# Avalon_PDU.net
KiCad netlist of a schematic drawn in Altium Designer
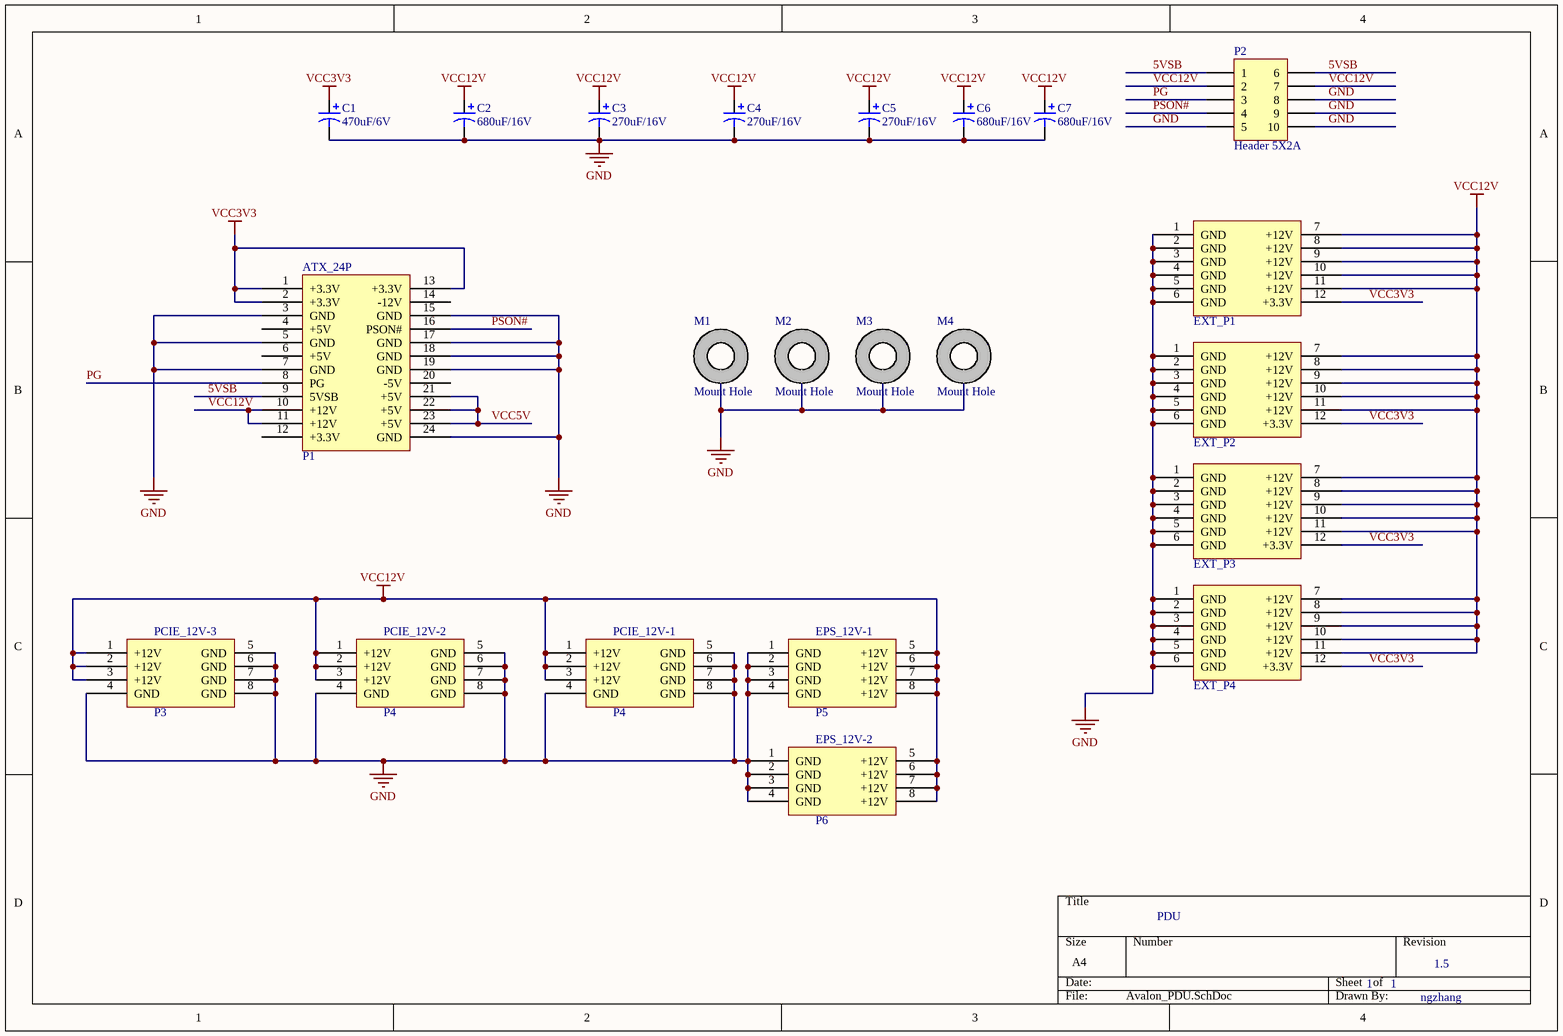
[diagram p0: Avalon_PDU.SchDoc]

(export (version "E")
  (design (tool "Eeschema 10.0.6"))
  (components
    (comp (ref "ATX_24P")
      (value "P1")
      (footprint "ATX_24P")
      (libsource (lib "power_adapter") (part "ATX_24P"))
    )
    (comp (ref "C1")
      (value "470uF/6V")
      (footprint "CAP8X8")
      (description "Polarized Capacitor (Surface Mount)")
      (fields (field (name "PUBLISHER") "Altium Limited"))
      (libsource (lib "S6_2") (part "Cap Pol3"))
    )
    (comp (ref "C2")
      (value "680uF/16V")
      (footprint "CAP8X8")
      (description "Polarized Capacitor (Surface Mount)")
      (fields (field (name "PUBLISHER") "Altium Limited"))
      (libsource (lib "S6_2") (part "Cap Pol3"))
    )
    (comp (ref "C3")
      (value "270uF/16V")
      (footprint "CAP8X8")
      (description "Polarized Capacitor (Surface Mount)")
      (fields (field (name "PUBLISHER") "Altium Limited"))
      (libsource (lib "S6_2") (part "Cap Pol3"))
    )
    (comp (ref "C4")
      (value "270uF/16V")
      (footprint "CAP8X8")
      (description "Polarized Capacitor (Surface Mount)")
      (fields (field (name "PUBLISHER") "Altium Limited"))
      (libsource (lib "S6_2") (part "Cap Pol3"))
    )
    (comp (ref "C5")
      (value "270uF/16V")
      (footprint "CAP8X8")
      (description "Polarized Capacitor (Surface Mount)")
      (fields (field (name "PUBLISHER") "Altium Limited"))
      (libsource (lib "S6_2") (part "Cap Pol3"))
    )
    (comp (ref "C6")
      (value "680uF/16V")
      (footprint "CAP8X8")
      (description "Polarized Capacitor (Surface Mount)")
      (fields (field (name "PUBLISHER") "Altium Limited"))
      (libsource (lib "S6_2") (part "Cap Pol3"))
    )
    (comp (ref "C7")
      (value "680uF/16V")
      (footprint "CAP8X8")
      (description "Polarized Capacitor (Surface Mount)")
      (fields (field (name "PUBLISHER") "Altium Limited"))
      (libsource (lib "S6_2") (part "Cap Pol3"))
    )
    (comp (ref "EPS_12V-1")
      (value "P5")
      (footprint "EPS_12V")
      (libsource (lib "power_adapter") (part "EPS_12V"))
    )
    (comp (ref "EPS_12V-2")
      (value "P6")
      (footprint "EPS_12V")
      (libsource (lib "power_adapter") (part "EPS_12V"))
    )
    (comp (ref "EXT_P1")
      (value "PWR_12P")
      (footprint "PWR_12PIN")
      (libsource (lib "power_adapter") (part "PWR_12P"))
    )
    (comp (ref "EXT_P2")
      (value "PWR_12P")
      (footprint "PWR_12PIN")
      (libsource (lib "power_adapter") (part "PWR_12P"))
    )
    (comp (ref "EXT_P3")
      (value "PWR_12P")
      (footprint "PWR_12PIN")
      (libsource (lib "power_adapter") (part "PWR_12P"))
    )
    (comp (ref "EXT_P4")
      (value "PWR_12P")
      (footprint "PWR_12PIN")
      (libsource (lib "power_adapter") (part "PWR_12P"))
    )
    (comp (ref "M1") (value "Mount Hole") (footprint "MHOLE2") (libsource (lib "S6_2") (part "M_Hole")))
    (comp (ref "M2") (value "Mount Hole") (footprint "MHOLE2") (libsource (lib "S6_2") (part "M_Hole")))
    (comp (ref "M3") (value "Mount Hole") (footprint "MHOLE2") (libsource (lib "S6_2") (part "M_Hole")))
    (comp (ref "M4") (value "Mount Hole") (footprint "MHOLE2") (libsource (lib "S6_2") (part "M_Hole")))
    (comp (ref "P2")
      (value "Header 5X2A")
      (footprint "PWR_10PIN")
      (description "Header, 5-Pin, Dual row")
      (fields (field (name "PUBLISHER") "Altium Limited"))
      (libsource (lib "Miscellaneous Connectors") (part "Header 5X2A"))
    )
    (comp (ref "PCIE_12V-1")
      (value "P4")
      (footprint "PCIE_12V_V")
      (libsource (lib "power_adapter") (part "PCIE_12V"))
    )
    (comp (ref "PCIE_12V-2")
      (value "P4")
      (footprint "PCIE_12V_V")
      (libsource (lib "power_adapter") (part "PCIE_12V"))
    )
    (comp (ref "PCIE_12V-3")
      (value "P3")
      (footprint "PCIE_12V_V")
      (libsource (lib "power_adapter") (part "PCIE_12V"))
    )
  )
  (nets
    (net (code "1") (name "/5VSB") (class "Default")
      (node (ref "ATX_24P") (pin "9") (pinfunction "5VSB_9") (pintype "passive"))
      (node (ref "P2") (pin "1") (pinfunction "1_1") (pintype "passive"))
      (node (ref "P2") (pin "6") (pinfunction "6_6") (pintype "passive"))
    )
    (net (code "2") (name "/PG") (class "Default")
      (node (ref "ATX_24P") (pin "8") (pinfunction "PG_8") (pintype "passive"))
      (node (ref "P2") (pin "3") (pinfunction "3_3") (pintype "passive"))
    )
    (net (code "3") (name "/PSON#") (class "Default")
      (node (ref "ATX_24P") (pin "16") (pinfunction "PSON#_16") (pintype "passive"))
      (node (ref "P2") (pin "4") (pinfunction "4_4") (pintype "passive"))
    )
    (net (code "4") (name "/VCC5V") (class "Default")
      (node (ref "ATX_24P") (pin "21") (pinfunction "+5V_21") (pintype "passive"))
      (node (ref "ATX_24P") (pin "22") (pinfunction "+5V_22") (pintype "passive"))
      (node (ref "ATX_24P") (pin "23") (pinfunction "+5V_23") (pintype "passive"))
    )
    (net (code "5") (name "GND") (class "Default")
      (node (ref "ATX_24P") (pin "15") (pinfunction "GND_15") (pintype "passive"))
      (node (ref "ATX_24P") (pin "17") (pinfunction "GND_17") (pintype "passive"))
      (node (ref "ATX_24P") (pin "18") (pinfunction "GND_18") (pintype "passive"))
      (node (ref "ATX_24P") (pin "19") (pinfunction "GND_19") (pintype "passive"))
      (node (ref "ATX_24P") (pin "24") (pinfunction "GND_24") (pintype "passive"))
      (node (ref "ATX_24P") (pin "3") (pinfunction "GND_3") (pintype "passive"))
      (node (ref "ATX_24P") (pin "5") (pinfunction "GND_5") (pintype "passive"))
      (node (ref "ATX_24P") (pin "7") (pinfunction "GND_7") (pintype "passive"))
      (node (ref "C1") (pin "2") (pinfunction "2_2") (pintype "passive"))
      (node (ref "C2") (pin "2") (pinfunction "2_2") (pintype "passive"))
      (node (ref "C3") (pin "2") (pinfunction "2_2") (pintype "passive"))
      (node (ref "C4") (pin "2") (pinfunction "2_2") (pintype "passive"))
      (node (ref "C5") (pin "2") (pinfunction "2_2") (pintype "passive"))
      (node (ref "C6") (pin "2") (pinfunction "2_2") (pintype "passive"))
      (node (ref "C7") (pin "2") (pinfunction "2_2") (pintype "passive"))
      (node (ref "EPS_12V-1") (pin "1") (pinfunction "GND_1") (pintype "passive"))
      (node (ref "EPS_12V-1") (pin "2") (pinfunction "GND_2") (pintype "passive"))
      (node (ref "EPS_12V-1") (pin "3") (pinfunction "GND_3") (pintype "passive"))
      (node (ref "EPS_12V-1") (pin "4") (pinfunction "GND_4") (pintype "passive"))
      (node (ref "EPS_12V-2") (pin "1") (pinfunction "GND_1") (pintype "passive"))
      (node (ref "EPS_12V-2") (pin "2") (pinfunction "GND_2") (pintype "passive"))
      (node (ref "EPS_12V-2") (pin "3") (pinfunction "GND_3") (pintype "passive"))
      (node (ref "EPS_12V-2") (pin "4") (pinfunction "GND_4") (pintype "passive"))
      (node (ref "EXT_P1") (pin "1") (pinfunction "GND_1") (pintype "passive"))
      (node (ref "EXT_P1") (pin "2") (pinfunction "GND_2") (pintype "passive"))
      (node (ref "EXT_P1") (pin "3") (pinfunction "GND_3") (pintype "passive"))
      (node (ref "EXT_P1") (pin "4") (pinfunction "GND_4") (pintype "passive"))
      (node (ref "EXT_P1") (pin "5") (pinfunction "GND_5") (pintype "passive"))
      (node (ref "EXT_P1") (pin "6") (pinfunction "GND_6") (pintype "passive"))
      (node (ref "EXT_P2") (pin "1") (pinfunction "GND_1") (pintype "passive"))
      (node (ref "EXT_P2") (pin "2") (pinfunction "GND_2") (pintype "passive"))
      (node (ref "EXT_P2") (pin "3") (pinfunction "GND_3") (pintype "passive"))
      (node (ref "EXT_P2") (pin "4") (pinfunction "GND_4") (pintype "passive"))
      (node (ref "EXT_P2") (pin "5") (pinfunction "GND_5") (pintype "passive"))
      (node (ref "EXT_P2") (pin "6") (pinfunction "GND_6") (pintype "passive"))
      (node (ref "EXT_P3") (pin "1") (pinfunction "GND_1") (pintype "passive"))
      (node (ref "EXT_P3") (pin "2") (pinfunction "GND_2") (pintype "passive"))
      (node (ref "EXT_P3") (pin "3") (pinfunction "GND_3") (pintype "passive"))
      (node (ref "EXT_P3") (pin "4") (pinfunction "GND_4") (pintype "passive"))
      (node (ref "EXT_P3") (pin "5") (pinfunction "GND_5") (pintype "passive"))
      (node (ref "EXT_P3") (pin "6") (pinfunction "GND_6") (pintype "passive"))
      (node (ref "EXT_P4") (pin "1") (pinfunction "GND_1") (pintype "passive"))
      (node (ref "EXT_P4") (pin "2") (pinfunction "GND_2") (pintype "passive"))
      (node (ref "EXT_P4") (pin "3") (pinfunction "GND_3") (pintype "passive"))
      (node (ref "EXT_P4") (pin "4") (pinfunction "GND_4") (pintype "passive"))
      (node (ref "EXT_P4") (pin "5") (pinfunction "GND_5") (pintype "passive"))
      (node (ref "EXT_P4") (pin "6") (pinfunction "GND_6") (pintype "passive"))
      (node (ref "M1") (pin "0") (pinfunction "PIN_0") (pintype "power_in"))
      (node (ref "M2") (pin "0") (pinfunction "PIN_0") (pintype "power_in"))
      (node (ref "M3") (pin "0") (pinfunction "PIN_0") (pintype "power_in"))
      (node (ref "M4") (pin "0") (pinfunction "PIN_0") (pintype "power_in"))
      (node (ref "P2") (pin "10") (pinfunction "10_10") (pintype "passive"))
      (node (ref "P2") (pin "5") (pinfunction "5_5") (pintype "passive"))
      (node (ref "P2") (pin "8") (pinfunction "8_8") (pintype "passive"))
      (node (ref "P2") (pin "9") (pinfunction "9_9") (pintype "passive"))
      (node (ref "PCIE_12V-1") (pin "4") (pinfunction "GND_4") (pintype "passive"))
      (node (ref "PCIE_12V-1") (pin "5") (pinfunction "GND_5") (pintype "passive"))
      (node (ref "PCIE_12V-1") (pin "6") (pinfunction "GND_6") (pintype "passive"))
      (node (ref "PCIE_12V-1") (pin "7") (pinfunction "GND_7") (pintype "passive"))
      (node (ref "PCIE_12V-1") (pin "8") (pinfunction "GND_8") (pintype "passive"))
      (node (ref "PCIE_12V-2") (pin "4") (pinfunction "GND_4") (pintype "passive"))
      (node (ref "PCIE_12V-2") (pin "5") (pinfunction "GND_5") (pintype "passive"))
      (node (ref "PCIE_12V-2") (pin "6") (pinfunction "GND_6") (pintype "passive"))
      (node (ref "PCIE_12V-2") (pin "7") (pinfunction "GND_7") (pintype "passive"))
      (node (ref "PCIE_12V-2") (pin "8") (pinfunction "GND_8") (pintype "passive"))
      (node (ref "PCIE_12V-3") (pin "4") (pinfunction "GND_4") (pintype "passive"))
      (node (ref "PCIE_12V-3") (pin "5") (pinfunction "GND_5") (pintype "passive"))
      (node (ref "PCIE_12V-3") (pin "6") (pinfunction "GND_6") (pintype "passive"))
      (node (ref "PCIE_12V-3") (pin "7") (pinfunction "GND_7") (pintype "passive"))
      (node (ref "PCIE_12V-3") (pin "8") (pinfunction "GND_8") (pintype "passive"))
    )
    (net (code "6") (name "VCC3V3") (class "Default")
      (node (ref "ATX_24P") (pin "1") (pinfunction "+3.3V_1") (pintype "passive"))
      (node (ref "ATX_24P") (pin "13") (pinfunction "+3.3V_13") (pintype "passive"))
      (node (ref "ATX_24P") (pin "2") (pinfunction "+3.3V_2") (pintype "passive"))
      (node (ref "C1") (pin "1") (pinfunction "1_1") (pintype "passive"))
      (node (ref "EXT_P1") (pin "12") (pinfunction "+3.3V_12") (pintype "passive"))
      (node (ref "EXT_P2") (pin "12") (pinfunction "+3.3V_12") (pintype "passive"))
      (node (ref "EXT_P3") (pin "12") (pinfunction "+3.3V_12") (pintype "passive"))
      (node (ref "EXT_P4") (pin "12") (pinfunction "+3.3V_12") (pintype "passive"))
    )
    (net (code "7") (name "VCC12V") (class "Default")
      (node (ref "ATX_24P") (pin "10") (pinfunction "+12V_10") (pintype "passive"))
      (node (ref "ATX_24P") (pin "11") (pinfunction "+12V_11") (pintype "passive"))
      (node (ref "C2") (pin "1") (pinfunction "1_1") (pintype "passive"))
      (node (ref "C3") (pin "1") (pinfunction "1_1") (pintype "passive"))
      (node (ref "C4") (pin "1") (pinfunction "1_1") (pintype "passive"))
      (node (ref "C5") (pin "1") (pinfunction "1_1") (pintype "passive"))
      (node (ref "C6") (pin "1") (pinfunction "1_1") (pintype "passive"))
      (node (ref "C7") (pin "1") (pinfunction "1_1") (pintype "passive"))
      (node (ref "EPS_12V-1") (pin "5") (pinfunction "+12V_5") (pintype "passive"))
      (node (ref "EPS_12V-1") (pin "6") (pinfunction "+12V_6") (pintype "passive"))
      (node (ref "EPS_12V-1") (pin "7") (pinfunction "+12V_7") (pintype "passive"))
      (node (ref "EPS_12V-1") (pin "8") (pinfunction "+12V_8") (pintype "passive"))
      (node (ref "EPS_12V-2") (pin "5") (pinfunction "+12V_5") (pintype "passive"))
      (node (ref "EPS_12V-2") (pin "6") (pinfunction "+12V_6") (pintype "passive"))
      (node (ref "EPS_12V-2") (pin "7") (pinfunction "+12V_7") (pintype "passive"))
      (node (ref "EPS_12V-2") (pin "8") (pinfunction "+12V_8") (pintype "passive"))
      (node (ref "EXT_P1") (pin "10") (pinfunction "+12V_10") (pintype "passive"))
      (node (ref "EXT_P1") (pin "11") (pinfunction "+12V_11") (pintype "passive"))
      (node (ref "EXT_P1") (pin "7") (pinfunction "+12V_7") (pintype "passive"))
      (node (ref "EXT_P1") (pin "8") (pinfunction "+12V_8") (pintype "passive"))
      (node (ref "EXT_P1") (pin "9") (pinfunction "+12V_9") (pintype "passive"))
      (node (ref "EXT_P2") (pin "10") (pinfunction "+12V_10") (pintype "passive"))
      (node (ref "EXT_P2") (pin "11") (pinfunction "+12V_11") (pintype "passive"))
      (node (ref "EXT_P2") (pin "7") (pinfunction "+12V_7") (pintype "passive"))
      (node (ref "EXT_P2") (pin "8") (pinfunction "+12V_8") (pintype "passive"))
      (node (ref "EXT_P2") (pin "9") (pinfunction "+12V_9") (pintype "passive"))
      (node (ref "EXT_P3") (pin "10") (pinfunction "+12V_10") (pintype "passive"))
      (node (ref "EXT_P3") (pin "11") (pinfunction "+12V_11") (pintype "passive"))
      (node (ref "EXT_P3") (pin "7") (pinfunction "+12V_7") (pintype "passive"))
      (node (ref "EXT_P3") (pin "8") (pinfunction "+12V_8") (pintype "passive"))
      (node (ref "EXT_P3") (pin "9") (pinfunction "+12V_9") (pintype "passive"))
      (node (ref "EXT_P4") (pin "10") (pinfunction "+12V_10") (pintype "passive"))
      (node (ref "EXT_P4") (pin "11") (pinfunction "+12V_11") (pintype "passive"))
      (node (ref "EXT_P4") (pin "7") (pinfunction "+12V_7") (pintype "passive"))
      (node (ref "EXT_P4") (pin "8") (pinfunction "+12V_8") (pintype "passive"))
      (node (ref "EXT_P4") (pin "9") (pinfunction "+12V_9") (pintype "passive"))
      (node (ref "P2") (pin "2") (pinfunction "2_2") (pintype "passive"))
      (node (ref "P2") (pin "7") (pinfunction "7_7") (pintype "passive"))
      (node (ref "PCIE_12V-1") (pin "1") (pinfunction "+12V_1") (pintype "passive"))
      (node (ref "PCIE_12V-1") (pin "2") (pinfunction "+12V_2") (pintype "passive"))
      (node (ref "PCIE_12V-1") (pin "3") (pinfunction "+12V_3") (pintype "passive"))
      (node (ref "PCIE_12V-2") (pin "1") (pinfunction "+12V_1") (pintype "passive"))
      (node (ref "PCIE_12V-2") (pin "2") (pinfunction "+12V_2") (pintype "passive"))
      (node (ref "PCIE_12V-2") (pin "3") (pinfunction "+12V_3") (pintype "passive"))
      (node (ref "PCIE_12V-3") (pin "1") (pinfunction "+12V_1") (pintype "passive"))
      (node (ref "PCIE_12V-3") (pin "2") (pinfunction "+12V_2") (pintype "passive"))
      (node (ref "PCIE_12V-3") (pin "3") (pinfunction "+12V_3") (pintype "passive"))
    )
    (net (code "8") (name "unconnected-(ATX_24P-+3.3V-Pad12)") (class "Default")
      (node (ref "ATX_24P") (pin "12") (pinfunction "+3.3V_12") (pintype "passive"))
    )
    (net (code "9") (name "unconnected-(ATX_24P-+5V-Pad4)") (class "Default")
      (node (ref "ATX_24P") (pin "4") (pinfunction "+5V_4") (pintype "passive"))
    )
    (net (code "10") (name "unconnected-(ATX_24P-+5V-Pad6)") (class "Default")
      (node (ref "ATX_24P") (pin "6") (pinfunction "+5V_6") (pintype "passive"))
    )
    (net (code "11") (name "unconnected-(ATX_24P--5V-Pad20)") (class "Default")
      (node (ref "ATX_24P") (pin "20") (pinfunction "-5V_20") (pintype "passive"))
    )
    (net (code "12") (name "unconnected-(ATX_24P--12V-Pad14)") (class "Default")
      (node (ref "ATX_24P") (pin "14") (pinfunction "-12V_14") (pintype "passive"))
    )
  )
)
